# Main.net
KiCad netlist of a schematic drawn in Altium Designer
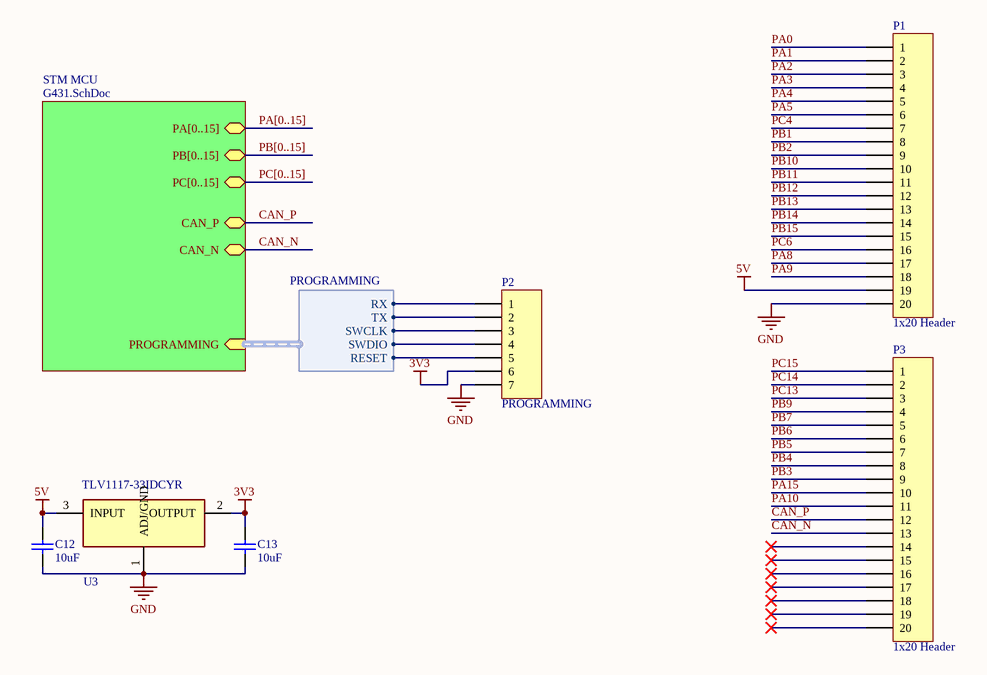
[diagram p0: Main.SchDoc]

(export (version "E")
  (design (tool "Eeschema 10.0.6"))
  (components
    (comp (ref "C12")
      (value "10uF")
      (footprint "0805 - Capacitor")
      (description "Nonpolarized Capacitor")
      (fields (field (name "Comment") "Capacitor - Nonpolarized"))
      (libsource (lib "General") (part "Capacitor - Nonpolarized"))
    )
    (comp (ref "C13")
      (value "10uF")
      (footprint "0805 - Capacitor")
      (description "Nonpolarized Capacitor")
      (fields (field (name "Comment") "Capacitor - Nonpolarized"))
      (libsource (lib "General") (part "Capacitor - Nonpolarized"))
    )
    (comp (ref "P1")
      (value "1x20 Header")
      (footprint "HDR1X20")
      (description "1x20 Pin Header")
      (libsource (lib "GeneralConnectors") (part "1x20 Header"))
    )
    (comp (ref "P2")
      (value "PROGRAMMING")
      (footprint "HDR1X7")
      (description "1x7 Pin Header")
      (libsource (lib "GeneralConnectors") (part "1x7 Header"))
    )
    (comp (ref "P3")
      (value "1x20 Header")
      (footprint "HDR1X20")
      (description "1x20 Pin Header")
      (libsource (lib "GeneralConnectors") (part "1x20 Header"))
    )
    (comp (ref "U3")
      (value "TLV1117-33IDCYR")
      (footprint "TLV1117")
      (description "Linear Voltage Regulator IC 3.3V 800MA SOT223-4")
      (fields (field (name "MANUFACTURER") "Texas Instruments"))
      (libsource (lib "GeneralComponents") (part "TLV1117-33IDCYR"))
    )
  )
  (nets
    (net (code "21") (name "/CAN_N") (class "Default")
      (node (ref "P3") (pin "13") (pinfunction "13_13") (pintype "passive"))
    )
    (net (code "22") (name "/CAN_P") (class "Default")
      (node (ref "P3") (pin "12") (pinfunction "12_12") (pintype "passive"))
    )
    (net (code "23") (name "/PA0") (class "Default")
      (node (ref "P1") (pin "1") (pinfunction "1_1") (pintype "passive"))
    )
    (net (code "24") (name "/PA1") (class "Default")
      (node (ref "P1") (pin "2") (pinfunction "2_2") (pintype "passive"))
    )
    (net (code "25") (name "/PA2") (class "Default")
      (node (ref "P1") (pin "3") (pinfunction "3_3") (pintype "passive"))
    )
    (net (code "26") (name "/PA3") (class "Default")
      (node (ref "P1") (pin "4") (pinfunction "4_4") (pintype "passive"))
    )
    (net (code "27") (name "/PA4") (class "Default")
      (node (ref "P1") (pin "5") (pinfunction "5_5") (pintype "passive"))
    )
    (net (code "28") (name "/PA5") (class "Default")
      (node (ref "P1") (pin "6") (pinfunction "6_6") (pintype "passive"))
    )
    (net (code "29") (name "/PA8") (class "Default")
      (node (ref "P1") (pin "17") (pinfunction "17_17") (pintype "passive"))
    )
    (net (code "30") (name "/PA9") (class "Default")
      (node (ref "P1") (pin "18") (pinfunction "18_18") (pintype "passive"))
    )
    (net (code "31") (name "/PA10") (class "Default")
      (node (ref "P3") (pin "11") (pinfunction "11_11") (pintype "passive"))
    )
    (net (code "32") (name "/PA15") (class "Default")
      (node (ref "P3") (pin "10") (pinfunction "10_10") (pintype "passive"))
    )
    (net (code "34") (name "/PB1") (class "Default")
      (node (ref "P1") (pin "8") (pinfunction "8_8") (pintype "passive"))
    )
    (net (code "35") (name "/PB2") (class "Default")
      (node (ref "P1") (pin "9") (pinfunction "9_9") (pintype "passive"))
    )
    (net (code "36") (name "/PB3") (class "Default")
      (node (ref "P3") (pin "9") (pinfunction "9_9") (pintype "passive"))
    )
    (net (code "37") (name "/PB4") (class "Default")
      (node (ref "P3") (pin "8") (pinfunction "8_8") (pintype "passive"))
    )
    (net (code "38") (name "/PB5") (class "Default")
      (node (ref "P3") (pin "7") (pinfunction "7_7") (pintype "passive"))
    )
    (net (code "39") (name "/PB6") (class "Default")
      (node (ref "P3") (pin "6") (pinfunction "6_6") (pintype "passive"))
    )
    (net (code "40") (name "/PB7") (class "Default")
      (node (ref "P3") (pin "5") (pinfunction "5_5") (pintype "passive"))
    )
    (net (code "41") (name "/PB9") (class "Default")
      (node (ref "P3") (pin "4") (pinfunction "4_4") (pintype "passive"))
    )
    (net (code "42") (name "/PB10") (class "Default")
      (node (ref "P1") (pin "10") (pinfunction "10_10") (pintype "passive"))
    )
    (net (code "43") (name "/PB11") (class "Default")
      (node (ref "P1") (pin "11") (pinfunction "11_11") (pintype "passive"))
    )
    (net (code "44") (name "/PB12") (class "Default")
      (node (ref "P1") (pin "12") (pinfunction "12_12") (pintype "passive"))
    )
    (net (code "45") (name "/PB13") (class "Default")
      (node (ref "P1") (pin "13") (pinfunction "13_13") (pintype "passive"))
    )
    (net (code "46") (name "/PB14") (class "Default")
      (node (ref "P1") (pin "14") (pinfunction "14_14") (pintype "passive"))
    )
    (net (code "47") (name "/PB15") (class "Default")
      (node (ref "P1") (pin "15") (pinfunction "15_15") (pintype "passive"))
    )
    (net (code "49") (name "/PC4") (class "Default")
      (node (ref "P1") (pin "7") (pinfunction "7_7") (pintype "passive"))
    )
    (net (code "50") (name "/PC6") (class "Default")
      (node (ref "P1") (pin "16") (pinfunction "16_16") (pintype "passive"))
    )
    (net (code "51") (name "/PC13") (class "Default")
      (node (ref "P3") (pin "3") (pinfunction "3_3") (pintype "passive"))
    )
    (net (code "52") (name "/PC14") (class "Default")
      (node (ref "P3") (pin "2") (pinfunction "2_2") (pintype "passive"))
    )
    (net (code "53") (name "/PC15") (class "Default")
      (node (ref "P3") (pin "1") (pinfunction "1_1") (pintype "passive"))
    )
    (net (code "55") (name "/RESET") (class "Default")
      (node (ref "P2") (pin "5") (pinfunction "5_5") (pintype "passive"))
    )
    (net (code "56") (name "/RX") (class "Default")
      (node (ref "P2") (pin "1") (pinfunction "1_1") (pintype "passive"))
    )
    (net (code "57") (name "/SWCLK") (class "Default")
      (node (ref "P2") (pin "3") (pinfunction "3_3") (pintype "passive"))
    )
    (net (code "58") (name "/SWDIO") (class "Default")
      (node (ref "P2") (pin "4") (pinfunction "4_4") (pintype "passive"))
    )
    (net (code "59") (name "/TX") (class "Default")
      (node (ref "P2") (pin "2") (pinfunction "2_2") (pintype "passive"))
    )
    (net (code "61") (name "3V3") (class "Default")
      (node (ref "C13") (pin "2") (pinfunction "2_2") (pintype "passive"))
      (node (ref "P2") (pin "6") (pinfunction "6_6") (pintype "passive"))
      (node (ref "U3") (pin "2") (pinfunction "OUTPUT_2") (pintype "passive"))
    )
    (net (code "62") (name "5V") (class "Default")
      (node (ref "C12") (pin "2") (pinfunction "2_2") (pintype "passive"))
      (node (ref "P1") (pin "19") (pinfunction "19_19") (pintype "passive"))
      (node (ref "U3") (pin "3") (pinfunction "INPUT_3") (pintype "passive"))
    )
    (net (code "63") (name "GND") (class "Default")
      (node (ref "C12") (pin "1") (pinfunction "1_1") (pintype "passive"))
      (node (ref "C13") (pin "1") (pinfunction "1_1") (pintype "passive"))
      (node (ref "P1") (pin "20") (pinfunction "20_20") (pintype "passive"))
      (node (ref "P2") (pin "7") (pinfunction "7_7") (pintype "passive"))
      (node (ref "U3") (pin "1") (pinfunction "ADJ/GND_1") (pintype "passive"))
    )
    (net (code "64") (name "unconnected-(P3-Pad14)") (class "Default")
      (node (ref "P3") (pin "14") (pinfunction "14_14") (pintype "passive+no_connect"))
    )
    (net (code "65") (name "unconnected-(P3-Pad15)") (class "Default")
      (node (ref "P3") (pin "15") (pinfunction "15_15") (pintype "passive+no_connect"))
    )
    (net (code "66") (name "unconnected-(P3-Pad16)") (class "Default")
      (node (ref "P3") (pin "16") (pinfunction "16_16") (pintype "passive+no_connect"))
    )
    (net (code "67") (name "unconnected-(P3-Pad17)") (class "Default")
      (node (ref "P3") (pin "17") (pinfunction "17_17") (pintype "passive+no_connect"))
    )
    (net (code "68") (name "unconnected-(P3-Pad18)") (class "Default")
      (node (ref "P3") (pin "18") (pinfunction "18_18") (pintype "passive+no_connect"))
    )
    (net (code "69") (name "unconnected-(P3-Pad19)") (class "Default")
      (node (ref "P3") (pin "19") (pinfunction "19_19") (pintype "passive+no_connect"))
    )
    (net (code "70") (name "unconnected-(P3-Pad20)") (class "Default")
      (node (ref "P3") (pin "20") (pinfunction "20_20") (pintype "passive+no_connect"))
    )
  )
)
